# brick_i2c_battery.net
KiCad netlist of a schematic drawn in EAGLE
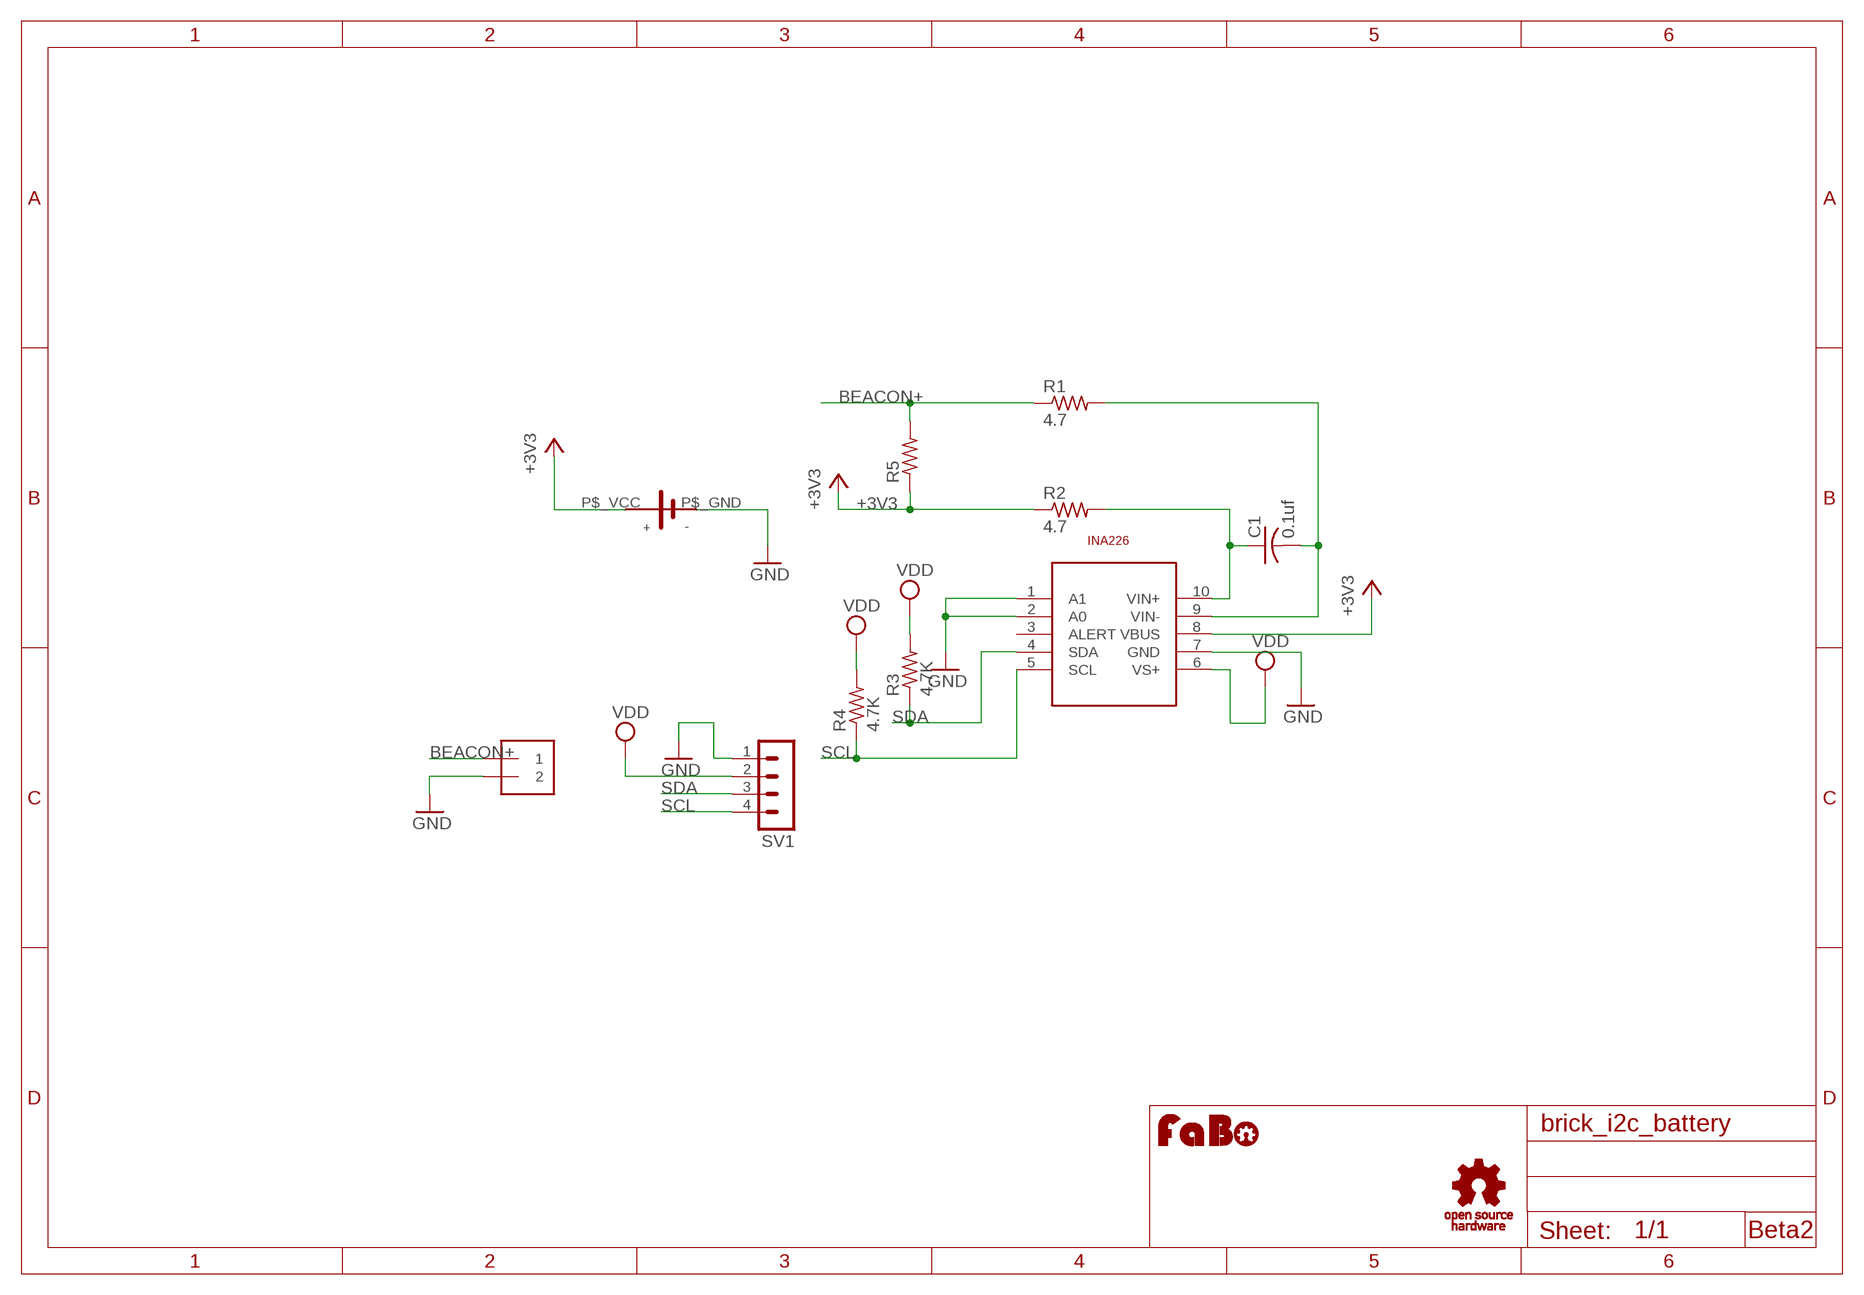
[diagram p0: schematic, sheet 1]

(export (version "E")
  (design (tool "Eeschema 10.0.6"))
  (components
    (comp (ref "C1")
      (value "0.1uf")
      (footprint "eagle-import:C0603")
      (libsource (lib "eagle-import") (part "C-USC0603"))
    )
    (comp (ref "INA1")
      (value "TI-INA226")
      (footprint "eagle-import:TI-INA226")
      (libsource (lib "eagle-import") (part "TI-INA226"))
    )
    (comp (ref "J1")
      (value "1X2-3.5MM")
      (footprint "eagle-import:1X2-3.5MM")
      (libsource (lib "eagle-import") (part "1X2-3.5MM"))
    )
    (comp (ref "R1")
      (value "4.7")
      (footprint "eagle-import:R0603")
      (libsource (lib "eagle-import") (part "R-US_R0603"))
    )
    (comp (ref "R2")
      (value "4.7")
      (footprint "eagle-import:R0603")
      (libsource (lib "eagle-import") (part "R-US_R0603"))
    )
    (comp (ref "R3")
      (value "4.7K")
      (footprint "eagle-import:R0603")
      (libsource (lib "eagle-import") (part "R-US_R0603"))
    )
    (comp (ref "R4")
      (value "4.7K")
      (footprint "eagle-import:R0603")
      (libsource (lib "eagle-import") (part "R-US_R0603"))
    )
    (comp (ref "R5")
      (value "R-US_R6332")
      (footprint "eagle-import:R6332")
      (libsource (lib "eagle-import") (part "R-US_R6332"))
    )
    (comp (ref "SV1")
      (value "MA04-1")
      (footprint "eagle-import:MA04-1")
      (libsource (lib "eagle-import") (part "MA04-1"))
    )
    (comp (ref "U$2")
      (value "SMTU2450")
      (footprint "eagle-import:SMTU2450")
      (libsource (lib "eagle-import") (part "SMTU2450"))
    )
    (comp (ref "U$3")
      (value "LOGO_FABO-S")
      (footprint "eagle-import:LOGO_FABO_S")
      (libsource (lib "eagle-import") (part "LOGO_FABO-S"))
    )
    (comp (ref "U$4")
      (value "LOGO_OSHW_T-S")
      (footprint "eagle-import:LOGO_OSHW_T_S")
      (libsource (lib "eagle-import") (part "LOGO_OSHW_T-S"))
    )
  )
  (nets
    (net (code "1") (name "+3V3") (class "Default")
      (node (ref "INA1") (pin "8") (pinfunction "VBUS_8") (pintype "bidirectional"))
      (node (ref "R2") (pin "1") (pinfunction "1_1") (pintype "passive"))
      (node (ref "R5") (pin "1") (pinfunction "1_1") (pintype "passive"))
      (node (ref "U$2") (pin "P$_VCC") (pinfunction "P$_VCC_P$_VCC") (pintype "bidirectional"))
    )
    (net (code "2") (name "/BEACON+") (class "Default")
      (node (ref "J1") (pin "1") (pinfunction "1_1") (pintype "passive"))
      (node (ref "R1") (pin "1") (pinfunction "1_1") (pintype "passive"))
      (node (ref "R5") (pin "2") (pinfunction "2_2") (pintype "passive"))
    )
    (net (code "3") (name "/SCL") (class "Default")
      (node (ref "INA1") (pin "5") (pinfunction "SCL_5") (pintype "bidirectional"))
      (node (ref "R4") (pin "1") (pinfunction "1_1") (pintype "passive"))
      (node (ref "SV1") (pin "4") (pinfunction "4_4") (pintype "passive"))
    )
    (net (code "4") (name "/SDA") (class "Default")
      (node (ref "INA1") (pin "4") (pinfunction "SDA_4") (pintype "bidirectional"))
      (node (ref "R3") (pin "1") (pinfunction "1_1") (pintype "passive"))
      (node (ref "SV1") (pin "3") (pinfunction "3_3") (pintype "passive"))
    )
    (net (code "5") (name "GND") (class "Default")
      (node (ref "INA1") (pin "1") (pinfunction "A1_1") (pintype "bidirectional"))
      (node (ref "INA1") (pin "2") (pinfunction "A0_2") (pintype "bidirectional"))
      (node (ref "INA1") (pin "7") (pinfunction "GND_7") (pintype "bidirectional"))
      (node (ref "J1") (pin "2") (pinfunction "2_2") (pintype "passive"))
      (node (ref "SV1") (pin "1") (pinfunction "1_1") (pintype "passive"))
      (node (ref "U$2") (pin "P$_GND") (pinfunction "P$_GND_P$_GND") (pintype "bidirectional"))
    )
    (net (code "6") (name "Net-(INA1-VIN+)") (class "Default")
      (node (ref "C1") (pin "1") (pinfunction "1_1") (pintype "passive"))
      (node (ref "INA1") (pin "10") (pinfunction "VIN+_10") (pintype "bidirectional"))
      (node (ref "R2") (pin "2") (pinfunction "2_2") (pintype "passive"))
    )
    (net (code "7") (name "Net-(INA1-VIN-)") (class "Default")
      (node (ref "C1") (pin "2") (pinfunction "2_2") (pintype "passive"))
      (node (ref "INA1") (pin "9") (pinfunction "VIN-_9") (pintype "bidirectional"))
      (node (ref "R1") (pin "2") (pinfunction "2_2") (pintype "passive"))
    )
    (net (code "8") (name "VDD") (class "Default")
      (node (ref "INA1") (pin "6") (pinfunction "VS+_6") (pintype "bidirectional"))
      (node (ref "R3") (pin "2") (pinfunction "2_2") (pintype "passive"))
      (node (ref "R4") (pin "2") (pinfunction "2_2") (pintype "passive"))
      (node (ref "SV1") (pin "2") (pinfunction "2_2") (pintype "passive"))
    )
    (net (code "9") (name "unconnected-(INA1-ALERT-Pad3)") (class "Default")
      (node (ref "INA1") (pin "3") (pinfunction "ALERT_3") (pintype "bidirectional"))
    )
  )
)
